# nightlight_bjt_b2.net
KiCad netlist of a schematic drawn in EAGLE
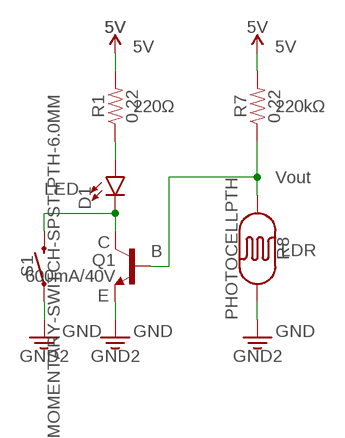
[diagram p0: schematic, sheet 1]

(export (version "E")
  (design (tool "Eeschema 10.0.6"))
  (components
    (comp (ref "D1")
      (value "LED5MM")
      (footprint "eagle-import:LED_5MM")
      (libsource (lib "eagle-import") (part "LED5MM"))
    )
    (comp (ref "Q1")
      (value "600mA/40V")
      (footprint "eagle-import:TO-92")
      (libsource (lib "eagle-import") (part "TRANS_NPN-P2N2222A"))
    )
    (comp (ref "R1")
      (value "0.22")
      (footprint "eagle-import:0805")
      (libsource (lib "eagle-import") (part "0.22OHM-0805-1/4W-1%"))
    )
    (comp (ref "R7")
      (value "0.22")
      (footprint "eagle-import:0805")
      (libsource (lib "eagle-import") (part "0.22OHM-0805-1/4W-1%"))
    )
    (comp (ref "R8")
      (value "PHOTOCELLPTH")
      (footprint "eagle-import:PHOTOCELL")
      (libsource (lib "eagle-import") (part "PHOTOCELLPTH"))
    )
    (comp (ref "S1")
      (value "MOMENTARY-SWITCH-SPST-PTH-6.0MM")
      (footprint "eagle-import:TACTILE_SWITCH_PTH_6.0MM")
      (libsource (lib "eagle-import") (part "MOMENTARY-SWITCH-SPST-PTH-6.0MM"))
    )
  )
  (nets
    (net (code "1") (name "5V") (class "Default")
      (node (ref "R1") (pin "2") (pinfunction "2_2") (pintype "passive"))
      (node (ref "R7") (pin "2") (pinfunction "2_2") (pintype "passive"))
    )
    (net (code "2") (name "GND2") (class "Default")
      (node (ref "Q1") (pin "3") (pinfunction "E_3") (pintype "passive"))
      (node (ref "R8") (pin "2") (pinfunction "P$2_2") (pintype "bidirectional"))
      (node (ref "S1") (pin "1") (pinfunction "1_1") (pintype "passive"))
    )
    (net (code "3") (name "Net-(D1-C)") (class "Default")
      (node (ref "D1") (pin "K") (pinfunction "C_K") (pintype "passive"))
      (node (ref "Q1") (pin "1") (pinfunction "C_1") (pintype "passive"))
      (node (ref "S1") (pin "3") (pinfunction "2_3") (pintype "passive"))
    )
    (net (code "4") (name "Net-(D1-PadA)") (class "Default")
      (node (ref "D1") (pin "A") (pinfunction "A_A") (pintype "passive"))
      (node (ref "R1") (pin "1") (pinfunction "1_1") (pintype "passive"))
    )
    (net (code "5") (name "Net-(Q1-B)") (class "Default")
      (node (ref "Q1") (pin "2") (pinfunction "B_2") (pintype "passive"))
      (node (ref "R7") (pin "1") (pinfunction "1_1") (pintype "passive"))
      (node (ref "R8") (pin "1") (pinfunction "P$1_1") (pintype "bidirectional"))
    )
  )
)
